# AUDIO.net
KiCad netlist of a schematic drawn in Altium Designer
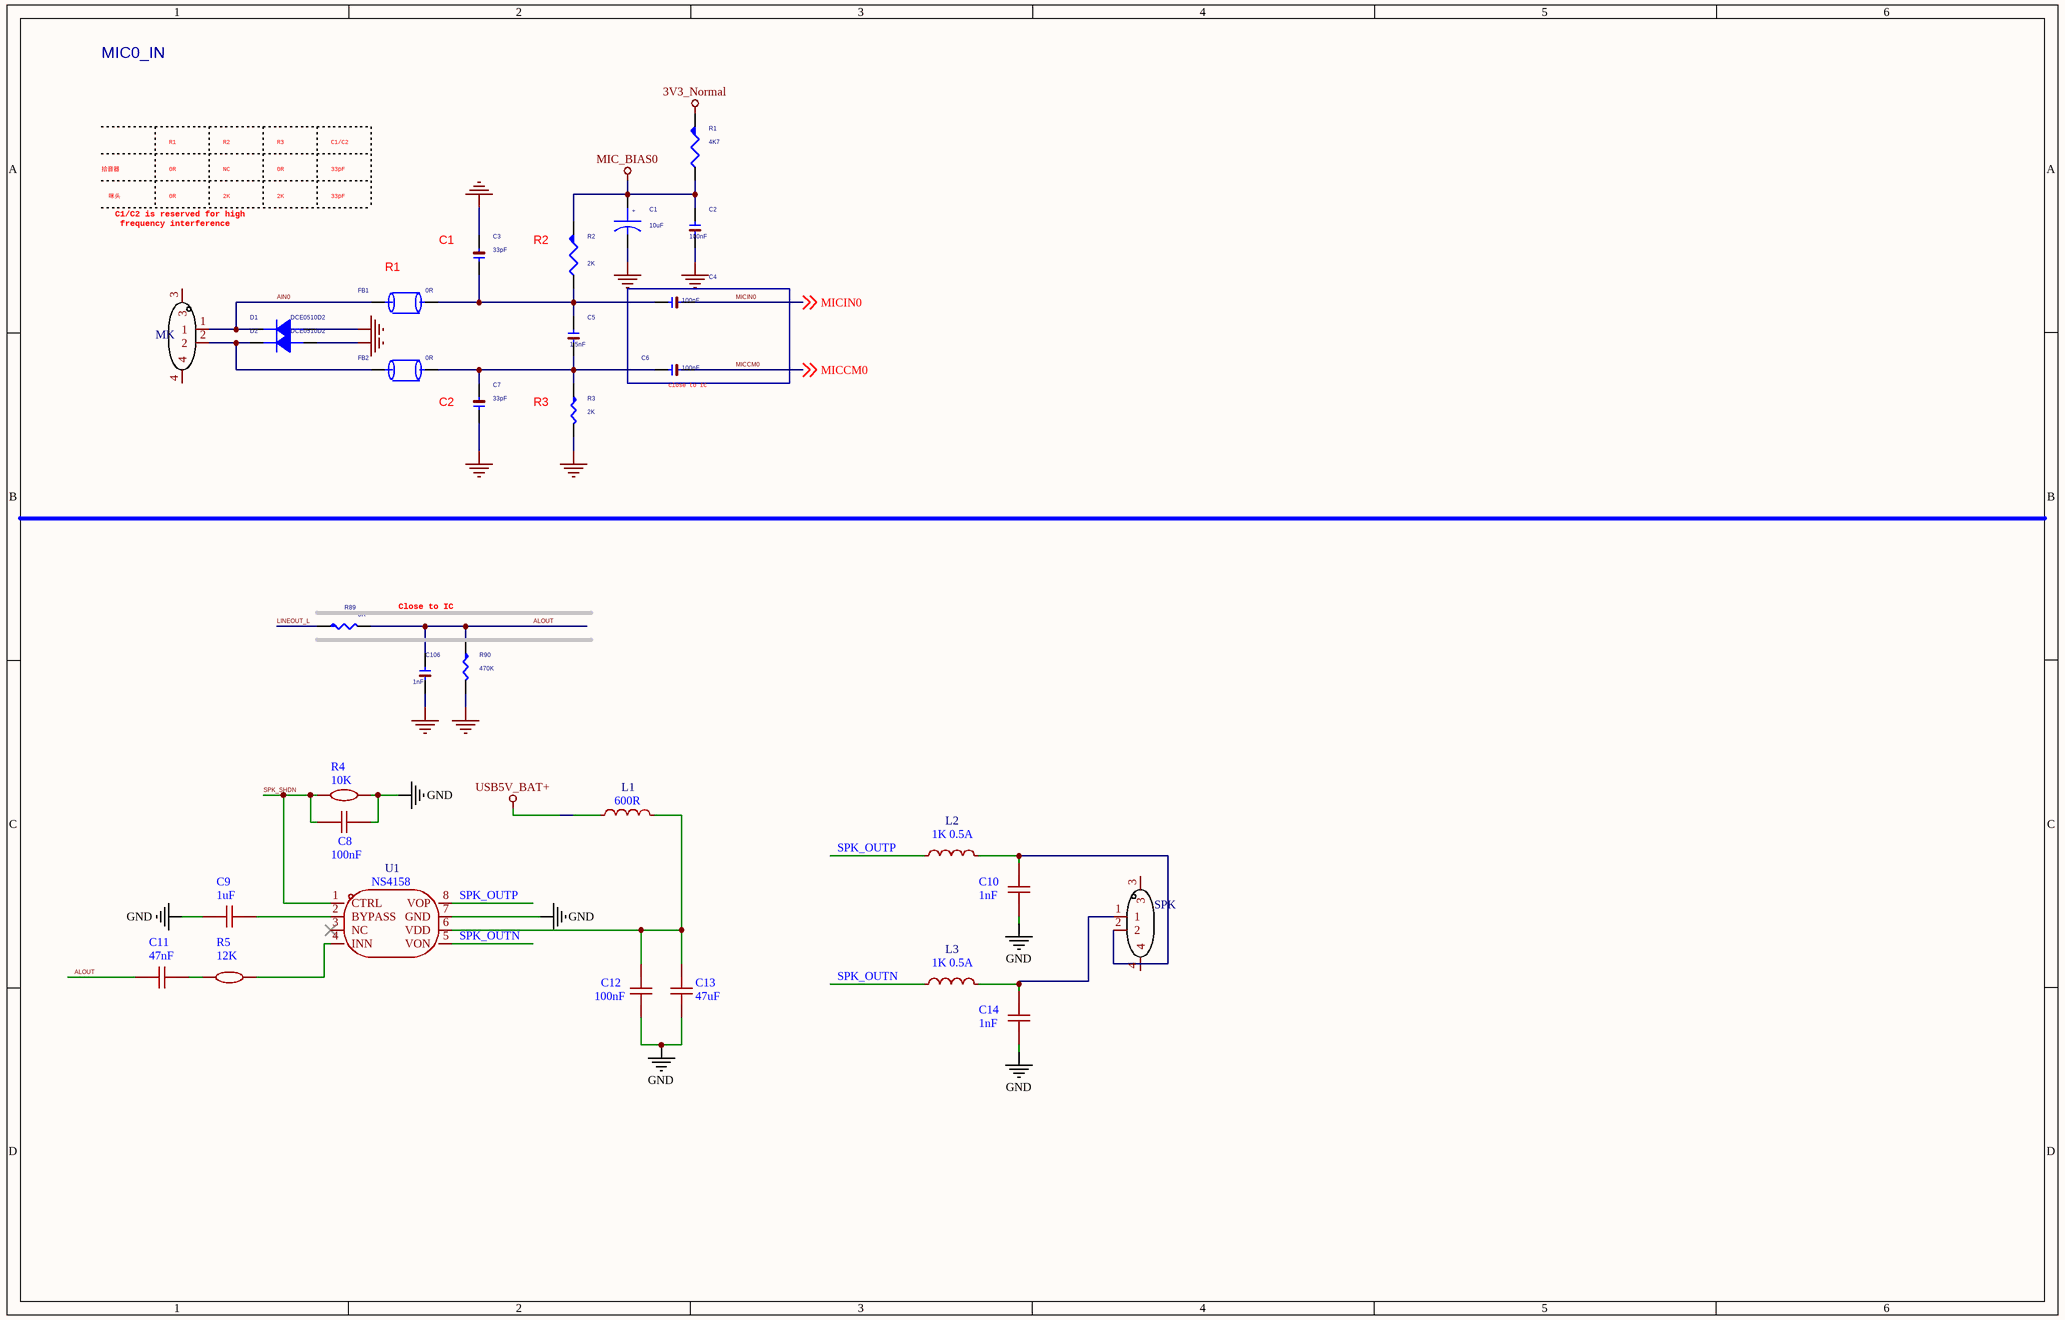
[diagram p0: AUDIO.SchDoc]

(export (version "E")
  (design (tool "Eeschema 10.0.6"))
  (components
    (comp (ref "C1") (value "10uF") (footprint "C0603") (libsource (lib "*") (part "CAP POL")))
    (comp (ref "C2") (value "100nF") (footprint "C0402") (libsource (lib "*") (part "C0805_10uF")))
    (comp (ref "C3") (value "33pF") (footprint "C0402") (libsource (lib "*") (part "C0402")))
    (comp (ref "C4") (value "100nF") (footprint "C0402") (libsource (lib "") (part "C0805_10uF_1")))
    (comp (ref "C5") (value "1.5nF") (footprint "C0402") (libsource (lib "*") (part "C0805_10uF")))
    (comp (ref "C6") (value "100nF") (footprint "C0402") (libsource (lib "") (part "C0805_10uF_1")))
    (comp (ref "C7") (value "33pF") (footprint "C0402") (libsource (lib "*") (part "C0402")))
    (comp (ref "C8")
      (value "100nF")
      (footprint "C0402")
      (libsource (lib "altium-import") (part "root_0_CAP_0805_"))
    )
    (comp (ref "C9")
      (value "1uF")
      (footprint "C0805")
      (libsource (lib "altium-import") (part "root_0_CAP_0805_"))
    )
    (comp (ref "C10")
      (value "1nF")
      (footprint "C0805")
      (libsource (lib "altium-import") (part "root_1_CAP_0805_"))
    )
    (comp (ref "C11")
      (value "47nF")
      (footprint "C0805")
      (libsource (lib "altium-import") (part "root_0_CAP_0805_"))
    )
    (comp (ref "C12")
      (value "100nF")
      (footprint "C0805")
      (libsource (lib "altium-import") (part "root_1_CAP_0805_"))
    )
    (comp (ref "C13")
      (value "47uF")
      (footprint "C1206")
      (libsource (lib "altium-import") (part "root_1_CAP_1206_"))
    )
    (comp (ref "C14")
      (value "1nF")
      (footprint "C0805")
      (libsource (lib "altium-import") (part "root_1_CAP_0805_"))
    )
    (comp (ref "C106") (value "1nF") (footprint "C0805") (libsource (lib "*") (part "C0805_10uF")))
    (comp (ref "CON1")
      (value "MK")
      (footprint "CONN-SMD_2P-P1.25-LT")
      (fields (field (name "MANUFACTURER PART") "HC-1.25-2PLT"))
      (libsource (lib "altium-import") (part "root_0_mirrored_HC-1.25-2PLT_"))
    )
    (comp (ref "CON2")
      (value "SPK")
      (footprint "CONN-SMD_2.0-2PLT")
      (fields (field (name "MANUFACTURER PART") "HC-1.25-2PLT"))
      (libsource (lib "altium-import") (part "root_0_HC-1.25-2PLT_"))
    )
    (comp (ref "D1")
      (value "DCE0510D2")
      (footprint "D0402_0.55x0.6")
      (libsource (lib "*") (part "DIODE_Dup1"))
    )
    (comp (ref "D2")
      (value "DCE0510D2")
      (footprint "D0402_0.55x0.6")
      (libsource (lib "*") (part "DIODE_Dup1"))
    )
    (comp (ref "FB1")
      (value "0R")
      (footprint "R0402")
      (description "BEAD/0402/120ohm/200MA")
      (fields (field (name "PART_NUMBER") "49223"))
      (libsource (lib "*") (part "BEAD"))
    )
    (comp (ref "FB2")
      (value "0R")
      (footprint "R0402")
      (description "BEAD/0402/120ohm/200MA")
      (fields (field (name "PART_NUMBER") "49223"))
      (libsource (lib "*") (part "BEAD"))
    )
    (comp (ref "L1")
      (value "600R")
      (footprint "L1206")
      (libsource (lib "altium-import") (part "root_0_CBW321609U601T_"))
    )
    (comp (ref "L2")
      (value "1K 0.5A")
      (footprint "L0805")
      (fields (field (name "MANUFACTURER PART") "SBK201209T-102Y-N"))
      (libsource (lib "altium-import") (part "root_0_SBK201209T-102Y-N_"))
    )
    (comp (ref "L3")
      (value "1K 0.5A")
      (footprint "L0805")
      (libsource (lib "altium-import") (part "root_0_SBK201209T-102Y-N_"))
    )
    (comp (ref "R1") (value "4K7") (footprint "R0402") (libsource (lib "*") (part "R-PIN-Mark")))
    (comp (ref "R2") (value "2K") (footprint "R0402") (libsource (lib "*") (part "R-PIN-Mark")))
    (comp (ref "R3") (value "2K") (footprint "R0402") (libsource (lib "*") (part "R0402")))
    (comp (ref "R4")
      (value "10K")
      (footprint "R0402")
      (libsource (lib "altium-import") (part "root_0_Res_0805_"))
    )
    (comp (ref "R5")
      (value "12K")
      (footprint "R0402")
      (libsource (lib "altium-import") (part "root_0_Res_0805_"))
    )
    (comp (ref "R89")
      (value "0R")
      (footprint "R0402")
      (description "[ 330R +-5% ](0402); NPO")
      (fields (field (name "CREATOR") "Alan.Liu#6135/0920796617"))
      (libsource (lib "*") (part "R0402_330R 5%"))
    )
    (comp (ref "R90") (value "470K") (footprint "R0402") (libsource (lib "*") (part "R0402")))
    (comp (ref "U1")
      (value "NS4158")
      (footprint "SOIC-8_L4.9-W3.9-P1.27-LS6.0-BL")
      (libsource (lib "altium-import") (part "root_0_NS4158_"))
    )
  )
  (nets
    (net (code "1") (name "/AIN0") (class "Default")
      (node (ref "CON1") (pin "1") (pinfunction "1_1") (pintype "passive"))
      (node (ref "D1") (pin "2") (pinfunction "K_2") (pintype "passive"))
      (node (ref "FB1") (pin "1") (pinfunction "1_1") (pintype "passive"))
    )
    (net (code "2") (name "/ALOUT") (class "Default")
      (node (ref "C106") (pin "1") (pinfunction "1_1") (pintype "passive"))
      (node (ref "C11") (pin "1") (pinfunction "1_1") (pintype "passive"))
      (node (ref "R89") (pin "2") (pinfunction "2_2") (pintype "passive"))
      (node (ref "R90") (pin "1") (pinfunction "1_1") (pintype "passive"))
    )
    (net (code "3") (name "/LINEOUT_L") (class "Default")
      (node (ref "R89") (pin "1") (pinfunction "1_1") (pintype "passive"))
    )
    (net (code "4") (name "/SPK_OUTN") (class "Default")
      (node (ref "L3") (pin "1") (pinfunction "1_1") (pintype "passive"))
      (node (ref "U1") (pin "5") (pinfunction "VON_5") (pintype "passive"))
    )
    (net (code "5") (name "/SPK_OUTP") (class "Default")
      (node (ref "L2") (pin "1") (pinfunction "1_1") (pintype "passive"))
      (node (ref "U1") (pin "8") (pinfunction "VOP_8") (pintype "passive"))
    )
    (net (code "6") (name "/SPK_SHDN") (class "Default")
      (node (ref "C8") (pin "1") (pinfunction "1_1") (pintype "passive"))
      (node (ref "R4") (pin "1") (pinfunction "1_1") (pintype "passive"))
      (node (ref "U1") (pin "1") (pinfunction "CTRL_1") (pintype "passive"))
    )
    (net (code "7") (name "3V3_Normal") (class "Default")
      (node (ref "R1") (pin "1") (pinfunction "1_1") (pintype "passive"))
    )
    (net (code "8") (name "GND") (class "Default")
      (node (ref "C1") (pin "2") (pinfunction "2_2") (pintype "passive"))
      (node (ref "C10") (pin "1") (pinfunction "1_1") (pintype "passive"))
      (node (ref "C106") (pin "2") (pinfunction "2_2") (pintype "passive"))
      (node (ref "C12") (pin "1") (pinfunction "1_1") (pintype "passive"))
      (node (ref "C13") (pin "1") (pinfunction "1_1") (pintype "passive"))
      (node (ref "C14") (pin "1") (pinfunction "1_1") (pintype "passive"))
      (node (ref "C2") (pin "2") (pinfunction "2_2") (pintype "passive"))
      (node (ref "C3") (pin "1") (pinfunction "1_1") (pintype "passive"))
      (node (ref "C7") (pin "2") (pinfunction "2_2") (pintype "passive"))
      (node (ref "C8") (pin "2") (pinfunction "2_2") (pintype "passive"))
      (node (ref "C9") (pin "1") (pinfunction "1_1") (pintype "passive"))
      (node (ref "D1") (pin "1") (pinfunction "A_1") (pintype "passive"))
      (node (ref "D2") (pin "1") (pinfunction "A_1") (pintype "passive"))
      (node (ref "R3") (pin "2") (pinfunction "2_2") (pintype "passive"))
      (node (ref "R4") (pin "2") (pinfunction "2_2") (pintype "passive"))
      (node (ref "R90") (pin "2") (pinfunction "2_2") (pintype "passive"))
      (node (ref "U1") (pin "7") (pinfunction "GND_7") (pintype "passive"))
    )
    (net (code "9") (name "MICCM0") (class "Default")
      (node (ref "C6") (pin "2") (pinfunction "2_2") (pintype "passive"))
    )
    (net (code "10") (name "MICIN0") (class "Default")
      (node (ref "C4") (pin "2") (pinfunction "2_2") (pintype "passive"))
    )
    (net (code "11") (name "MIC_BIAS0") (class "Default")
      (node (ref "C1") (pin "1") (pinfunction "1_1") (pintype "passive"))
      (node (ref "C2") (pin "1") (pinfunction "1_1") (pintype "passive"))
      (node (ref "R1") (pin "2") (pinfunction "2_2") (pintype "passive"))
      (node (ref "R2") (pin "1") (pinfunction "1_1") (pintype "passive"))
    )
    (net (code "12") (name "Net-(C3-Pad2)") (class "Default")
      (node (ref "C3") (pin "2") (pinfunction "2_2") (pintype "passive"))
      (node (ref "C4") (pin "1") (pinfunction "1_1") (pintype "passive"))
      (node (ref "C5") (pin "1") (pinfunction "1_1") (pintype "passive"))
      (node (ref "FB1") (pin "2") (pinfunction "2_2") (pintype "passive"))
      (node (ref "R2") (pin "2") (pinfunction "2_2") (pintype "passive"))
    )
    (net (code "13") (name "Net-(C5-Pad2)") (class "Default")
      (node (ref "C5") (pin "2") (pinfunction "2_2") (pintype "passive"))
      (node (ref "C6") (pin "1") (pinfunction "1_1") (pintype "passive"))
      (node (ref "C7") (pin "1") (pinfunction "1_1") (pintype "passive"))
      (node (ref "FB2") (pin "2") (pinfunction "2_2") (pintype "passive"))
      (node (ref "R3") (pin "1") (pinfunction "1_1") (pintype "passive"))
    )
    (net (code "14") (name "Net-(C10-Pad2)") (class "Default")
      (node (ref "C10") (pin "2") (pinfunction "2_2") (pintype "passive"))
      (node (ref "CON2") (pin "2") (pinfunction "2_2") (pintype "passive"))
      (node (ref "L2") (pin "2") (pinfunction "2_2") (pintype "passive"))
    )
    (net (code "15") (name "Net-(C11-Pad2)") (class "Default")
      (node (ref "C11") (pin "2") (pinfunction "2_2") (pintype "passive"))
      (node (ref "R5") (pin "1") (pinfunction "1_1") (pintype "passive"))
    )
    (net (code "16") (name "Net-(C14-Pad2)") (class "Default")
      (node (ref "C14") (pin "2") (pinfunction "2_2") (pintype "passive"))
      (node (ref "CON2") (pin "1") (pinfunction "1_1") (pintype "passive"))
      (node (ref "L3") (pin "2") (pinfunction "2_2") (pintype "passive"))
    )
    (net (code "17") (name "Net-(D2-K)") (class "Default")
      (node (ref "CON1") (pin "2") (pinfunction "2_2") (pintype "passive"))
      (node (ref "D2") (pin "2") (pinfunction "K_2") (pintype "passive"))
      (node (ref "FB2") (pin "1") (pinfunction "1_1") (pintype "passive"))
    )
    (net (code "18") (name "Net-(U1-BYPASS)") (class "Default")
      (node (ref "C9") (pin "2") (pinfunction "2_2") (pintype "passive"))
      (node (ref "U1") (pin "2") (pinfunction "BYPASS_2") (pintype "passive"))
    )
    (net (code "19") (name "Net-(U1-INN)") (class "Default")
      (node (ref "R5") (pin "2") (pinfunction "2_2") (pintype "passive"))
      (node (ref "U1") (pin "4") (pinfunction "INN_4") (pintype "passive"))
    )
    (net (code "20") (name "Net-(U1-VDD)") (class "Default")
      (node (ref "C12") (pin "2") (pinfunction "2_2") (pintype "passive"))
      (node (ref "C13") (pin "2") (pinfunction "2_2") (pintype "passive"))
      (node (ref "L1") (pin "2") (pinfunction "2_2") (pintype "passive"))
      (node (ref "U1") (pin "6") (pinfunction "VDD_6") (pintype "passive"))
    )
    (net (code "21") (name "USB5V_BAT+") (class "Default")
      (node (ref "L1") (pin "1") (pinfunction "1_1") (pintype "passive"))
    )
    (net (code "22") (name "unconnected-(CON1-Pad3)") (class "Default")
      (node (ref "CON1") (pin "3") (pinfunction "3_3") (pintype "passive"))
    )
    (net (code "23") (name "unconnected-(CON1-Pad4)") (class "Default")
      (node (ref "CON1") (pin "4") (pinfunction "4_4") (pintype "passive"))
    )
    (net (code "24") (name "unconnected-(CON2-Pad3)") (class "Default")
      (node (ref "CON2") (pin "3") (pinfunction "3_3") (pintype "passive"))
    )
    (net (code "25") (name "unconnected-(CON2-Pad4)") (class "Default")
      (node (ref "CON2") (pin "4") (pinfunction "4_4") (pintype "passive"))
    )
    (net (code "26") (name "unconnected-(U1-NC-Pad3)") (class "Default")
      (node (ref "U1") (pin "3") (pinfunction "NC_3") (pintype "passive+no_connect"))
    )
  )
)
